# Sensor-amplification_V3.net
KiCad netlist of a schematic drawn in EAGLE
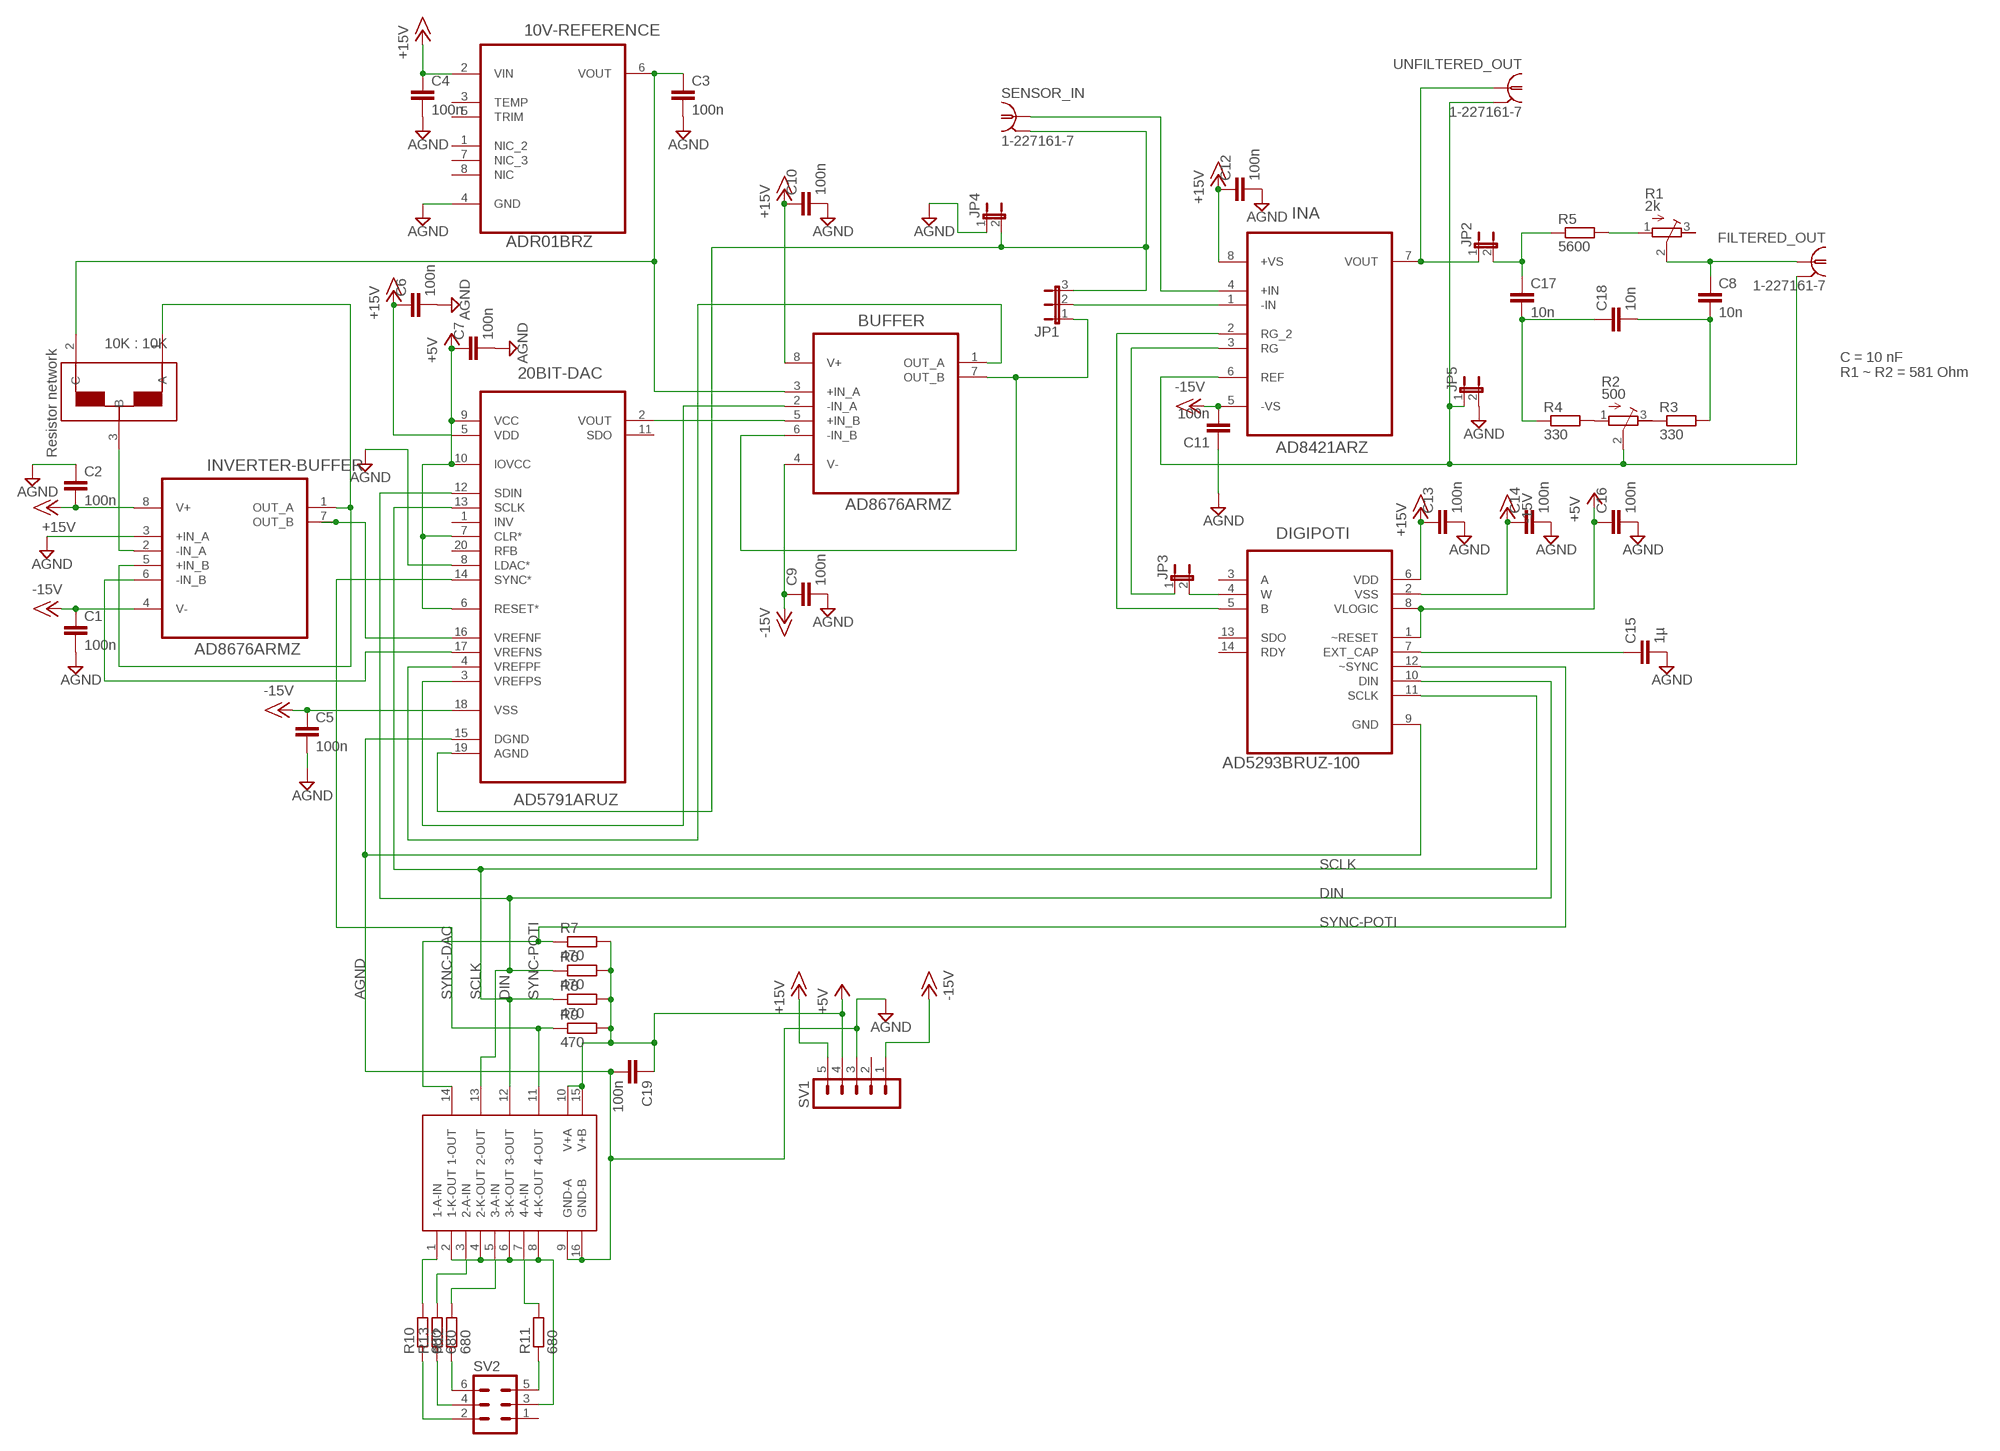
[diagram p0: schematic, sheet 1]

(export (version "E")
  (design (tool "Eeschema 10.0.6"))
  (components
    (comp (ref "10V-REFERENCE")
      (value "ADR01BRZ")
      (footprint "eagle-import:SOIC127P600X175-8N")
      (libsource (lib "eagle-import") (part "ADR01BRZ"))
    )
    (comp (ref "20BIT-DAC")
      (value "AD5791ARUZ")
      (footprint "eagle-import:SOP65P640X120-20N")
      (libsource (lib "eagle-import") (part "AD5791ARUZ"))
    )
    (comp (ref "BUFFER")
      (value "AD8676ARMZ")
      (footprint "eagle-import:SOP65P490X110-8N")
      (libsource (lib "eagle-import") (part "AD8676ARMZ"))
    )
    (comp (ref "C1")
      (value "100n")
      (footprint "eagle-import:C0603")
      (libsource (lib "eagle-import") (part "C-EUC0603"))
    )
    (comp (ref "C2")
      (value "100n")
      (footprint "eagle-import:C0603")
      (libsource (lib "eagle-import") (part "C-EUC0603"))
    )
    (comp (ref "C3")
      (value "100n")
      (footprint "eagle-import:C0603")
      (libsource (lib "eagle-import") (part "C-EUC0603"))
    )
    (comp (ref "C4")
      (value "100n")
      (footprint "eagle-import:C0603")
      (libsource (lib "eagle-import") (part "C-EUC0603"))
    )
    (comp (ref "C5")
      (value "100n")
      (footprint "eagle-import:C0603")
      (libsource (lib "eagle-import") (part "C-EUC0603"))
    )
    (comp (ref "C6")
      (value "100n")
      (footprint "eagle-import:C0603")
      (libsource (lib "eagle-import") (part "C-EUC0603"))
    )
    (comp (ref "C7")
      (value "100n")
      (footprint "eagle-import:C0603")
      (libsource (lib "eagle-import") (part "C-EUC0603"))
    )
    (comp (ref "C8")
      (value "10n")
      (footprint "eagle-import:C0805")
      (libsource (lib "eagle-import") (part "C-EUC0805"))
    )
    (comp (ref "C9")
      (value "100n")
      (footprint "eagle-import:C0603")
      (libsource (lib "eagle-import") (part "C-EUC0603"))
    )
    (comp (ref "C10")
      (value "100n")
      (footprint "eagle-import:C0603")
      (libsource (lib "eagle-import") (part "C-EUC0603"))
    )
    (comp (ref "C11")
      (value "100n")
      (footprint "eagle-import:C0603")
      (libsource (lib "eagle-import") (part "C-EUC0603"))
    )
    (comp (ref "C12")
      (value "100n")
      (footprint "eagle-import:C0603")
      (libsource (lib "eagle-import") (part "C-EUC0603"))
    )
    (comp (ref "C13")
      (value "100n")
      (footprint "eagle-import:C0603")
      (libsource (lib "eagle-import") (part "C-EUC0603"))
    )
    (comp (ref "C14")
      (value "100n")
      (footprint "eagle-import:C0603")
      (libsource (lib "eagle-import") (part "C-EUC0603"))
    )
    (comp (ref "C15")
      (value "1µ")
      (footprint "eagle-import:C0603")
      (libsource (lib "eagle-import") (part "C-EUC0603"))
    )
    (comp (ref "C16")
      (value "100n")
      (footprint "eagle-import:C0603")
      (libsource (lib "eagle-import") (part "C-EUC0603"))
    )
    (comp (ref "C17")
      (value "10n")
      (footprint "eagle-import:C0805")
      (libsource (lib "eagle-import") (part "C-EUC0805"))
    )
    (comp (ref "C18")
      (value "10n")
      (footprint "eagle-import:C0805")
      (libsource (lib "eagle-import") (part "C-EUC0805"))
    )
    (comp (ref "C19")
      (value "100n")
      (footprint "eagle-import:C0603")
      (libsource (lib "eagle-import") (part "C-EUC0603"))
    )
    (comp (ref "DIGIPOTI")
      (value "AD5293BRUZ-100")
      (footprint "eagle-import:SOP65P640X120-14N")
      (libsource (lib "eagle-import") (part "AD5293BRUZ-100"))
    )
    (comp (ref "FILTERED_OUT")
      (value "1-227161-7")
      (footprint "eagle-import:AMP_227161")
      (fields (field (name "MF") "TYCO ELECTRONICS"))
      (libsource (lib "eagle-import") (part "?2271611--7"))
    )
    (comp (ref "INA")
      (value "AD8421ARZ")
      (footprint "eagle-import:SOIC127P600X175-8N")
      (libsource (lib "eagle-import") (part "AD8421ARZ"))
    )
    (comp (ref "INVERTER-BUFFER")
      (value "AD8676ARMZ")
      (footprint "eagle-import:SOP65P490X110-8N")
      (libsource (lib "eagle-import") (part "AD8676ARMZ"))
    )
    (comp (ref "JP1")
      (value "JP2E")
      (footprint "eagle-import:JP2")
      (libsource (lib "eagle-import") (part "JP2E"))
    )
    (comp (ref "JP2")
      (value "JP1E")
      (footprint "eagle-import:JP1")
      (libsource (lib "eagle-import") (part "JP1E"))
    )
    (comp (ref "JP3")
      (value "JP1E")
      (footprint "eagle-import:JP1")
      (libsource (lib "eagle-import") (part "JP1E"))
    )
    (comp (ref "JP4")
      (value "JP1E")
      (footprint "eagle-import:JP1")
      (libsource (lib "eagle-import") (part "JP1E"))
    )
    (comp (ref "JP5")
      (value "JP1E")
      (footprint "eagle-import:JP1")
      (libsource (lib "eagle-import") (part "JP1E"))
    )
    (comp (ref "R1")
      (value "2k")
      (footprint "eagle-import:RTRIM64W")
      (libsource (lib "eagle-import") (part "R-TRIMM64W"))
    )
    (comp (ref "R2")
      (value "500")
      (footprint "eagle-import:RTRIM64W")
      (libsource (lib "eagle-import") (part "R-TRIMM64W"))
    )
    (comp (ref "R3")
      (value "330")
      (footprint "eagle-import:M1206")
      (libsource (lib "eagle-import") (part "R-EU_M1206"))
    )
    (comp (ref "R4")
      (value "330")
      (footprint "eagle-import:M1206")
      (libsource (lib "eagle-import") (part "R-EU_M1206"))
    )
    (comp (ref "R5")
      (value "5600")
      (footprint "eagle-import:M1206")
      (libsource (lib "eagle-import") (part "R-EU_M1206"))
    )
    (comp (ref "R6")
      (value "470")
      (footprint "eagle-import:M1206")
      (libsource (lib "eagle-import") (part "R-EU_M1206"))
    )
    (comp (ref "R7")
      (value "470")
      (footprint "eagle-import:M1206")
      (libsource (lib "eagle-import") (part "R-EU_M1206"))
    )
    (comp (ref "R8")
      (value "470")
      (footprint "eagle-import:M1206")
      (libsource (lib "eagle-import") (part "R-EU_M1206"))
    )
    (comp (ref "R9")
      (value "470")
      (footprint "eagle-import:M1206")
      (libsource (lib "eagle-import") (part "R-EU_M1206"))
    )
    (comp (ref "R10")
      (value "680")
      (footprint "eagle-import:M1206")
      (libsource (lib "eagle-import") (part "R-EU_M1206"))
    )
    (comp (ref "R11")
      (value "680")
      (footprint "eagle-import:M1206")
      (libsource (lib "eagle-import") (part "R-EU_M1206"))
    )
    (comp (ref "R12")
      (value "680")
      (footprint "eagle-import:M1206")
      (libsource (lib "eagle-import") (part "R-EU_M1206"))
    )
    (comp (ref "R13")
      (value "680")
      (footprint "eagle-import:M1206")
      (libsource (lib "eagle-import") (part "R-EU_M1206"))
    )
    (comp (ref "SENSOR_IN")
      (value "1-227161-7")
      (footprint "eagle-import:AMP_227161")
      (fields (field (name "MF") "TYCO ELECTRONICS"))
      (libsource (lib "eagle-import") (part "?2271611--7"))
    )
    (comp (ref "SV1")
      (value "MA05-1")
      (footprint "eagle-import:MA05-1")
      (libsource (lib "eagle-import") (part "MA05-1"))
    )
    (comp (ref "SV2")
      (value "MA03-2")
      (footprint "eagle-import:MA03-2")
      (libsource (lib "eagle-import") (part "MA03-2"))
    )
    (comp (ref "U$1")
      (value "MPMT2001AT5")
      (footprint "eagle-import:SOT23")
      (libsource (lib "eagle-import") (part "MPMT2001AT5"))
    )
    (comp (ref "U$2")
      (value "ACSL-6400")
      (footprint "eagle-import:SO16")
      (libsource (lib "eagle-import") (part "ACSL-6400"))
    )
    (comp (ref "UNFILTERED_OUT")
      (value "1-227161-7")
      (footprint "eagle-import:AMP_227161")
      (fields (field (name "MF") "TYCO ELECTRONICS"))
      (libsource (lib "eagle-import") (part "?2271611--7"))
    )
  )
  (nets
    (net (code "1") (name "+5V") (class "Default")
      (node (ref "20BIT-DAC") (pin "10") (pinfunction "IOVCC_10") (pintype "power_in"))
      (node (ref "20BIT-DAC") (pin "6") (pinfunction "RESET*_6") (pintype "input"))
      (node (ref "20BIT-DAC") (pin "7") (pinfunction "CLR*_7") (pintype "input"))
      (node (ref "20BIT-DAC") (pin "9") (pinfunction "VCC_9") (pintype "power_in"))
      (node (ref "C16") (pin "1") (pinfunction "1_1") (pintype "passive"))
      (node (ref "C19") (pin "1") (pinfunction "1_1") (pintype "passive"))
      (node (ref "C7") (pin "1") (pinfunction "1_1") (pintype "passive"))
      (node (ref "DIGIPOTI") (pin "1") (pinfunction "~{RESET}_1") (pintype "input"))
      (node (ref "DIGIPOTI") (pin "8") (pinfunction "VLOGIC_8") (pintype "power_in"))
      (node (ref "R6") (pin "2") (pinfunction "2_2") (pintype "passive"))
      (node (ref "R7") (pin "2") (pinfunction "2_2") (pintype "passive"))
      (node (ref "R8") (pin "2") (pinfunction "2_2") (pintype "passive"))
      (node (ref "R9") (pin "2") (pinfunction "2_2") (pintype "passive"))
      (node (ref "SV1") (pin "4") (pinfunction "4_4") (pintype "passive"))
      (node (ref "U$2") (pin "10") (pinfunction "V+A_10") (pintype "power_in"))
      (node (ref "U$2") (pin "15") (pinfunction "V+B_15") (pintype "power_in"))
    )
    (net (code "2") (name "+15V") (class "Default")
      (node (ref "10V-REFERENCE") (pin "2") (pinfunction "VIN_2") (pintype "input"))
      (node (ref "20BIT-DAC") (pin "5") (pinfunction "VDD_5") (pintype "power_in"))
      (node (ref "BUFFER") (pin "8") (pinfunction "V+_8") (pintype "power_in"))
      (node (ref "C10") (pin "1") (pinfunction "1_1") (pintype "passive"))
      (node (ref "C12") (pin "1") (pinfunction "1_1") (pintype "passive"))
      (node (ref "C13") (pin "1") (pinfunction "1_1") (pintype "passive"))
      (node (ref "C2") (pin "2") (pinfunction "2_2") (pintype "passive"))
      (node (ref "C4") (pin "1") (pinfunction "1_1") (pintype "passive"))
      (node (ref "C6") (pin "1") (pinfunction "1_1") (pintype "passive"))
      (node (ref "DIGIPOTI") (pin "6") (pinfunction "VDD_6") (pintype "power_in"))
      (node (ref "INA") (pin "8") (pinfunction "+VS_8") (pintype "power_in"))
      (node (ref "INVERTER-BUFFER") (pin "8") (pinfunction "V+_8") (pintype "power_in"))
      (node (ref "SV1") (pin "5") (pinfunction "5_5") (pintype "passive"))
    )
    (net (code "3") (name "-15V") (class "Default")
      (node (ref "20BIT-DAC") (pin "18") (pinfunction "VSS_18") (pintype "power_in"))
      (node (ref "BUFFER") (pin "4") (pinfunction "V-_4") (pintype "power_in"))
      (node (ref "C1") (pin "1") (pinfunction "1_1") (pintype "passive"))
      (node (ref "C11") (pin "2") (pinfunction "2_2") (pintype "passive"))
      (node (ref "C14") (pin "1") (pinfunction "1_1") (pintype "passive"))
      (node (ref "C5") (pin "1") (pinfunction "1_1") (pintype "passive"))
      (node (ref "C9") (pin "1") (pinfunction "1_1") (pintype "passive"))
      (node (ref "DIGIPOTI") (pin "2") (pinfunction "VSS_2") (pintype "power_in"))
      (node (ref "INA") (pin "5") (pinfunction "-VS_5") (pintype "power_in"))
      (node (ref "INVERTER-BUFFER") (pin "4") (pinfunction "V-_4") (pintype "power_in"))
      (node (ref "SV1") (pin "1") (pinfunction "1_1") (pintype "passive"))
    )
    (net (code "4") (name "/DIN") (class "Default")
      (node (ref "20BIT-DAC") (pin "12") (pinfunction "SDIN_12") (pintype "input"))
      (node (ref "DIGIPOTI") (pin "10") (pinfunction "DIN_10") (pintype "input"))
      (node (ref "R6") (pin "1") (pinfunction "1_1") (pintype "passive"))
      (node (ref "U$2") (pin "13") (pinfunction "2-OUT_13") (pintype "output"))
    )
    (net (code "5") (name "/SCLK") (class "Default")
      (node (ref "20BIT-DAC") (pin "13") (pinfunction "SCLK_13") (pintype "input"))
      (node (ref "DIGIPOTI") (pin "11") (pinfunction "SCLK_11") (pintype "input"))
      (node (ref "R8") (pin "1") (pinfunction "1_1") (pintype "passive"))
      (node (ref "U$2") (pin "12") (pinfunction "3-OUT_12") (pintype "output"))
    )
    (net (code "6") (name "/SYNC-DAC") (class "Default")
      (node (ref "20BIT-DAC") (pin "14") (pinfunction "SYNC*_14") (pintype "input"))
      (node (ref "R9") (pin "1") (pinfunction "1_1") (pintype "passive"))
      (node (ref "U$2") (pin "11") (pinfunction "4-OUT_11") (pintype "output"))
    )
    (net (code "7") (name "/SYNC-POTI") (class "Default")
      (node (ref "DIGIPOTI") (pin "12") (pinfunction "~{SYNC}_12") (pintype "input"))
      (node (ref "R7") (pin "1") (pinfunction "1_1") (pintype "passive"))
      (node (ref "U$2") (pin "14") (pinfunction "1-OUT_14") (pintype "output"))
    )
    (net (code "8") (name "AGND") (class "Default")
      (node (ref "10V-REFERENCE") (pin "4") (pinfunction "GND_4") (pintype "passive"))
      (node (ref "20BIT-DAC") (pin "15") (pinfunction "DGND_15") (pintype "passive"))
      (node (ref "20BIT-DAC") (pin "8") (pinfunction "LDAC*_8") (pintype "input"))
      (node (ref "C1") (pin "2") (pinfunction "2_2") (pintype "passive"))
      (node (ref "C10") (pin "2") (pinfunction "2_2") (pintype "passive"))
      (node (ref "C11") (pin "1") (pinfunction "1_1") (pintype "passive"))
      (node (ref "C12") (pin "2") (pinfunction "2_2") (pintype "passive"))
      (node (ref "C13") (pin "2") (pinfunction "2_2") (pintype "passive"))
      (node (ref "C14") (pin "2") (pinfunction "2_2") (pintype "passive"))
      (node (ref "C15") (pin "2") (pinfunction "2_2") (pintype "passive"))
      (node (ref "C16") (pin "2") (pinfunction "2_2") (pintype "passive"))
      (node (ref "C19") (pin "2") (pinfunction "2_2") (pintype "passive"))
      (node (ref "C2") (pin "1") (pinfunction "1_1") (pintype "passive"))
      (node (ref "C3") (pin "2") (pinfunction "2_2") (pintype "passive"))
      (node (ref "C4") (pin "2") (pinfunction "2_2") (pintype "passive"))
      (node (ref "C5") (pin "2") (pinfunction "2_2") (pintype "passive"))
      (node (ref "C6") (pin "2") (pinfunction "2_2") (pintype "passive"))
      (node (ref "C7") (pin "2") (pinfunction "2_2") (pintype "passive"))
      (node (ref "C9") (pin "2") (pinfunction "2_2") (pintype "passive"))
      (node (ref "DIGIPOTI") (pin "9") (pinfunction "GND_9") (pintype "passive"))
      (node (ref "INVERTER-BUFFER") (pin "3") (pinfunction "+IN_A_3") (pintype "input"))
      (node (ref "JP4") (pin "1") (pinfunction "1_1") (pintype "passive"))
      (node (ref "JP5") (pin "2") (pinfunction "2_2") (pintype "passive"))
      (node (ref "SV1") (pin "3") (pinfunction "3_3") (pintype "passive"))
      (node (ref "U$2") (pin "16") (pinfunction "GND-B_16") (pintype "power_in"))
      (node (ref "U$2") (pin "9") (pinfunction "GND-A_9") (pintype "power_in"))
    )
    (net (code "9") (name "Net-(10V-REFERENCE-VOUT)") (class "Default")
      (node (ref "10V-REFERENCE") (pin "6") (pinfunction "VOUT_6") (pintype "output"))
      (node (ref "BUFFER") (pin "3") (pinfunction "+IN_A_3") (pintype "input"))
      (node (ref "C3") (pin "1") (pinfunction "1_1") (pintype "passive"))
      (node (ref "U$1") (pin "2") (pinfunction "C_2") (pintype "passive"))
    )
    (net (code "10") (name "Net-(20BIT-DAC-AGND)") (class "Default")
      (node (ref "20BIT-DAC") (pin "19") (pinfunction "AGND_19") (pintype "passive"))
      (node (ref "JP1") (pin "3") (pinfunction "3_3") (pintype "passive"))
      (node (ref "JP4") (pin "2") (pinfunction "2_2") (pintype "passive"))
      (node (ref "SENSOR_IN") (pin "2") (pinfunction "2_2") (pintype "passive"))
    )
    (net (code "11") (name "Net-(20BIT-DAC-VOUT)") (class "Default")
      (node (ref "20BIT-DAC") (pin "2") (pinfunction "VOUT_2") (pintype "output"))
      (node (ref "BUFFER") (pin "5") (pinfunction "+IN_B_5") (pintype "input"))
    )
    (net (code "12") (name "Net-(20BIT-DAC-VREFNF)") (class "Default")
      (node (ref "20BIT-DAC") (pin "16") (pinfunction "VREFNF_16") (pintype "input"))
      (node (ref "INVERTER-BUFFER") (pin "7") (pinfunction "OUT_B_7") (pintype "output"))
    )
    (net (code "13") (name "Net-(20BIT-DAC-VREFNS)") (class "Default")
      (node (ref "20BIT-DAC") (pin "17") (pinfunction "VREFNS_17") (pintype "input"))
      (node (ref "INVERTER-BUFFER") (pin "6") (pinfunction "-IN_B_6") (pintype "input"))
    )
    (net (code "14") (name "Net-(20BIT-DAC-VREFPF)") (class "Default")
      (node (ref "20BIT-DAC") (pin "4") (pinfunction "VREFPF_4") (pintype "input"))
      (node (ref "BUFFER") (pin "1") (pinfunction "OUT_A_1") (pintype "output"))
    )
    (net (code "15") (name "Net-(20BIT-DAC-VREFPS)") (class "Default")
      (node (ref "20BIT-DAC") (pin "3") (pinfunction "VREFPS_3") (pintype "input"))
      (node (ref "BUFFER") (pin "2") (pinfunction "-IN_A_2") (pintype "input"))
    )
    (net (code "16") (name "Net-(BUFFER--IN_B)") (class "Default")
      (node (ref "BUFFER") (pin "6") (pinfunction "-IN_B_6") (pintype "input"))
      (node (ref "BUFFER") (pin "7") (pinfunction "OUT_B_7") (pintype "output"))
      (node (ref "JP1") (pin "1") (pinfunction "1_1") (pintype "passive"))
    )
    (net (code "17") (name "Net-(C17-Pad1)") (class "Default")
      (node (ref "C17") (pin "1") (pinfunction "1_1") (pintype "passive"))
      (node (ref "JP2") (pin "2") (pinfunction "2_2") (pintype "passive"))
      (node (ref "R5") (pin "1") (pinfunction "1_1") (pintype "passive"))
    )
    (net (code "18") (name "Net-(C17-Pad2)") (class "Default")
      (node (ref "C17") (pin "2") (pinfunction "2_2") (pintype "passive"))
      (node (ref "C18") (pin "1") (pinfunction "1_1") (pintype "passive"))
      (node (ref "R4") (pin "1") (pinfunction "1_1") (pintype "passive"))
    )
    (net (code "19") (name "Net-(C18-Pad2)") (class "Default")
      (node (ref "C18") (pin "2") (pinfunction "2_2") (pintype "passive"))
      (node (ref "C8") (pin "2") (pinfunction "2_2") (pintype "passive"))
      (node (ref "R3") (pin "2") (pinfunction "2_2") (pintype "passive"))
    )
    (net (code "20") (name "Net-(DIGIPOTI-B)") (class "Default")
      (node (ref "DIGIPOTI") (pin "5") (pinfunction "B_5") (pintype "passive"))
      (node (ref "INA") (pin "2") (pinfunction "RG_2_2") (pintype "input"))
    )
    (net (code "21") (name "Net-(DIGIPOTI-EXT_CAP)") (class "Default")
      (node (ref "C15") (pin "1") (pinfunction "1_1") (pintype "passive"))
      (node (ref "DIGIPOTI") (pin "7") (pinfunction "EXT_CAP_7") (pintype "passive"))
    )
    (net (code "22") (name "Net-(DIGIPOTI-W)") (class "Default")
      (node (ref "DIGIPOTI") (pin "4") (pinfunction "W_4") (pintype "passive"))
      (node (ref "JP3") (pin "2") (pinfunction "2_2") (pintype "passive"))
    )
    (net (code "23") (name "Net-(INA-+IN)") (class "Default")
      (node (ref "INA") (pin "4") (pinfunction "+IN_4") (pintype "input"))
      (node (ref "SENSOR_IN") (pin "1") (pinfunction "1_1") (pintype "passive"))
    )
    (net (code "24") (name "Net-(INA--IN)") (class "Default")
      (node (ref "INA") (pin "1") (pinfunction "-IN_1") (pintype "input"))
      (node (ref "JP1") (pin "2") (pinfunction "2_2") (pintype "passive"))
    )
    (net (code "25") (name "Net-(INA-REF)") (class "Default")
      (node (ref "FILTERED_OUT") (pin "2") (pinfunction "2_2") (pintype "passive"))
      (node (ref "INA") (pin "6") (pinfunction "REF_6") (pintype "input"))
      (node (ref "JP5") (pin "1") (pinfunction "1_1") (pintype "passive"))
      (node (ref "R2") (pin "2") (pinfunction "S_2") (pintype "passive"))
      (node (ref "UNFILTERED_OUT") (pin "2") (pinfunction "2_2") (pintype "passive"))
    )
    (net (code "26") (name "Net-(INA-RG)") (class "Default")
      (node (ref "INA") (pin "3") (pinfunction "RG_3") (pintype "input"))
      (node (ref "JP3") (pin "1") (pinfunction "1_1") (pintype "passive"))
    )
    (net (code "27") (name "Net-(INA-VOUT)") (class "Default")
      (node (ref "INA") (pin "7") (pinfunction "VOUT_7") (pintype "output"))
      (node (ref "JP2") (pin "1") (pinfunction "1_1") (pintype "passive"))
      (node (ref "UNFILTERED_OUT") (pin "1") (pinfunction "1_1") (pintype "passive"))
    )
    (net (code "28") (name "Net-(INVERTER-BUFFER-+IN_B)") (class "Default")
      (node (ref "INVERTER-BUFFER") (pin "1") (pinfunction "OUT_A_1") (pintype "output"))
      (node (ref "INVERTER-BUFFER") (pin "5") (pinfunction "+IN_B_5") (pintype "input"))
      (node (ref "U$1") (pin "1") (pinfunction "A_1") (pintype "passive"))
    )
    (net (code "29") (name "Net-(INVERTER-BUFFER--IN_A)") (class "Default")
      (node (ref "INVERTER-BUFFER") (pin "2") (pinfunction "-IN_A_2") (pintype "input"))
      (node (ref "U$1") (pin "3") (pinfunction "B_3") (pintype "passive"))
    )
    (net (code "30") (name "Net-(R1-A)") (class "Default")
      (node (ref "R1") (pin "1") (pinfunction "A_1") (pintype "passive"))
      (node (ref "R5") (pin "2") (pinfunction "2_2") (pintype "passive"))
    )
    (net (code "31") (name "Net-(R1-S)") (class "Default")
      (node (ref "C8") (pin "1") (pinfunction "1_1") (pintype "passive"))
      (node (ref "FILTERED_OUT") (pin "1") (pinfunction "1_1") (pintype "passive"))
      (node (ref "R1") (pin "2") (pinfunction "S_2") (pintype "passive"))
    )
    (net (code "32") (name "Net-(R2-A)") (class "Default")
      (node (ref "R2") (pin "1") (pinfunction "A_1") (pintype "passive"))
      (node (ref "R4") (pin "2") (pinfunction "2_2") (pintype "passive"))
    )
    (net (code "33") (name "Net-(R2-E)") (class "Default")
      (node (ref "R2") (pin "3") (pinfunction "E_3") (pintype "passive"))
      (node (ref "R3") (pin "1") (pinfunction "1_1") (pintype "passive"))
    )
    (net (code "34") (name "Net-(R10-Pad1)") (class "Default")
      (node (ref "R10") (pin "1") (pinfunction "1_1") (pintype "passive"))
      (node (ref "SV2") (pin "2") (pinfunction "2_2") (pintype "passive"))
    )
    (net (code "35") (name "Net-(R11-Pad1)") (class "Default")
      (node (ref "R11") (pin "1") (pinfunction "1_1") (pintype "passive"))
      (node (ref "SV2") (pin "5") (pinfunction "5_5") (pintype "passive"))
    )
    (net (code "36") (name "Net-(R12-Pad1)") (class "Default")
      (node (ref "R12") (pin "1") (pinfunction "1_1") (pintype "passive"))
      (node (ref "SV2") (pin "6") (pinfunction "6_6") (pintype "passive"))
    )
    (net (code "37") (name "Net-(R13-Pad1)") (class "Default")
      (node (ref "R13") (pin "1") (pinfunction "1_1") (pintype "passive"))
      (node (ref "SV2") (pin "4") (pinfunction "4_4") (pintype "passive"))
    )
    (net (code "38") (name "Net-(U$2-1-A-IN)") (class "Default")
      (node (ref "R10") (pin "2") (pinfunction "2_2") (pintype "passive"))
      (node (ref "U$2") (pin "1") (pinfunction "1-A-IN_1") (pintype "input"))
    )
    (net (code "39") (name "Net-(U$2-1-K-OUT)") (class "Default")
      (node (ref "SV2") (pin "3") (pinfunction "3_3") (pintype "passive"))
      (node (ref "U$2") (pin "2") (pinfunction "1-K-OUT_2") (pintype "output"))
      (node (ref "U$2") (pin "4") (pinfunction "2-K-OUT_4") (pintype "output"))
      (node (ref "U$2") (pin "6") (pinfunction "3-K-OUT_6") (pintype "output"))
      (node (ref "U$2") (pin "8") (pinfunction "4-K-OUT_8") (pintype "output"))
    )
    (net (code "40") (name "Net-(U$2-2-A-IN)") (class "Default")
      (node (ref "R13") (pin "2") (pinfunction "2_2") (pintype "passive"))
      (node (ref "U$2") (pin "3") (pinfunction "2-A-IN_3") (pintype "input"))
    )
    (net (code "41") (name "Net-(U$2-3-A-IN)") (class "Default")
      (node (ref "R12") (pin "2") (pinfunction "2_2") (pintype "passive"))
      (node (ref "U$2") (pin "5") (pinfunction "3-A-IN_5") (pintype "input"))
    )
    (net (code "42") (name "Net-(U$2-4-A-IN)") (class "Default")
      (node (ref "R11") (pin "2") (pinfunction "2_2") (pintype "passive"))
      (node (ref "U$2") (pin "7") (pinfunction "4-A-IN_7") (pintype "input"))
    )
    (net (code "43") (name "unconnected-(10V-REFERENCE-NIC-Pad8)") (class "Default")
      (node (ref "10V-REFERENCE") (pin "8") (pinfunction "NIC_8") (pintype "no_connect"))
    )
    (net (code "44") (name "unconnected-(10V-REFERENCE-NIC_2-Pad1)") (class "Default")
      (node (ref "10V-REFERENCE") (pin "1") (pinfunction "NIC_2_1") (pintype "no_connect"))
    )
    (net (code "45") (name "unconnected-(10V-REFERENCE-NIC_3-Pad7)") (class "Default")
      (node (ref "10V-REFERENCE") (pin "7") (pinfunction "NIC_3_7") (pintype "no_connect"))
    )
    (net (code "46") (name "unconnected-(10V-REFERENCE-TEMP-Pad3)") (class "Default")
      (node (ref "10V-REFERENCE") (pin "3") (pinfunction "TEMP_3") (pintype "passive"))
    )
    (net (code "47") (name "unconnected-(10V-REFERENCE-TRIM-Pad5)") (class "Default")
      (node (ref "10V-REFERENCE") (pin "5") (pinfunction "TRIM_5") (pintype "passive"))
    )
    (net (code "48") (name "unconnected-(20BIT-DAC-INV-Pad1)") (class "Default")
      (node (ref "20BIT-DAC") (pin "1") (pinfunction "INV_1") (pintype "input"))
    )
    (net (code "49") (name "unconnected-(20BIT-DAC-RFB-Pad20)") (class "Default")
      (node (ref "20BIT-DAC") (pin "20") (pinfunction "RFB_20") (pintype "passive"))
    )
    (net (code "50") (name "unconnected-(20BIT-DAC-SDO-Pad11)") (class "Default")
      (node (ref "20BIT-DAC") (pin "11") (pinfunction "SDO_11") (pintype "output"))
    )
    (net (code "51") (name "unconnected-(DIGIPOTI-A-Pad3)") (class "Default")
      (node (ref "DIGIPOTI") (pin "3") (pinfunction "A_3") (pintype "passive"))
    )
    (net (code "52") (name "unconnected-(DIGIPOTI-RDY-Pad14)") (class "Default")
      (node (ref "DIGIPOTI") (pin "14") (pinfunction "RDY_14") (pintype "output"))
    )
    (net (code "53") (name "unconnected-(DIGIPOTI-SDO-Pad13)") (class "Default")
      (node (ref "DIGIPOTI") (pin "13") (pinfunction "SDO_13") (pintype "output"))
    )
    (net (code "54") (name "unconnected-(R1-E-Pad3)") (class "Default")
      (node (ref "R1") (pin "3") (pinfunction "E_3") (pintype "passive"))
    )
    (net (code "55") (name "unconnected-(SV1-Pad2)") (class "Default")
      (node (ref "SV1") (pin "2") (pinfunction "2_2") (pintype "passive"))
    )
    (net (code "56") (name "unconnected-(SV2-Pad1)") (class "Default")
      (node (ref "SV2") (pin "1") (pinfunction "1_1") (pintype "passive"))
    )
  )
)
